# SCH_BO.net
KiCad netlist of a schematic drawn in Altium Designer
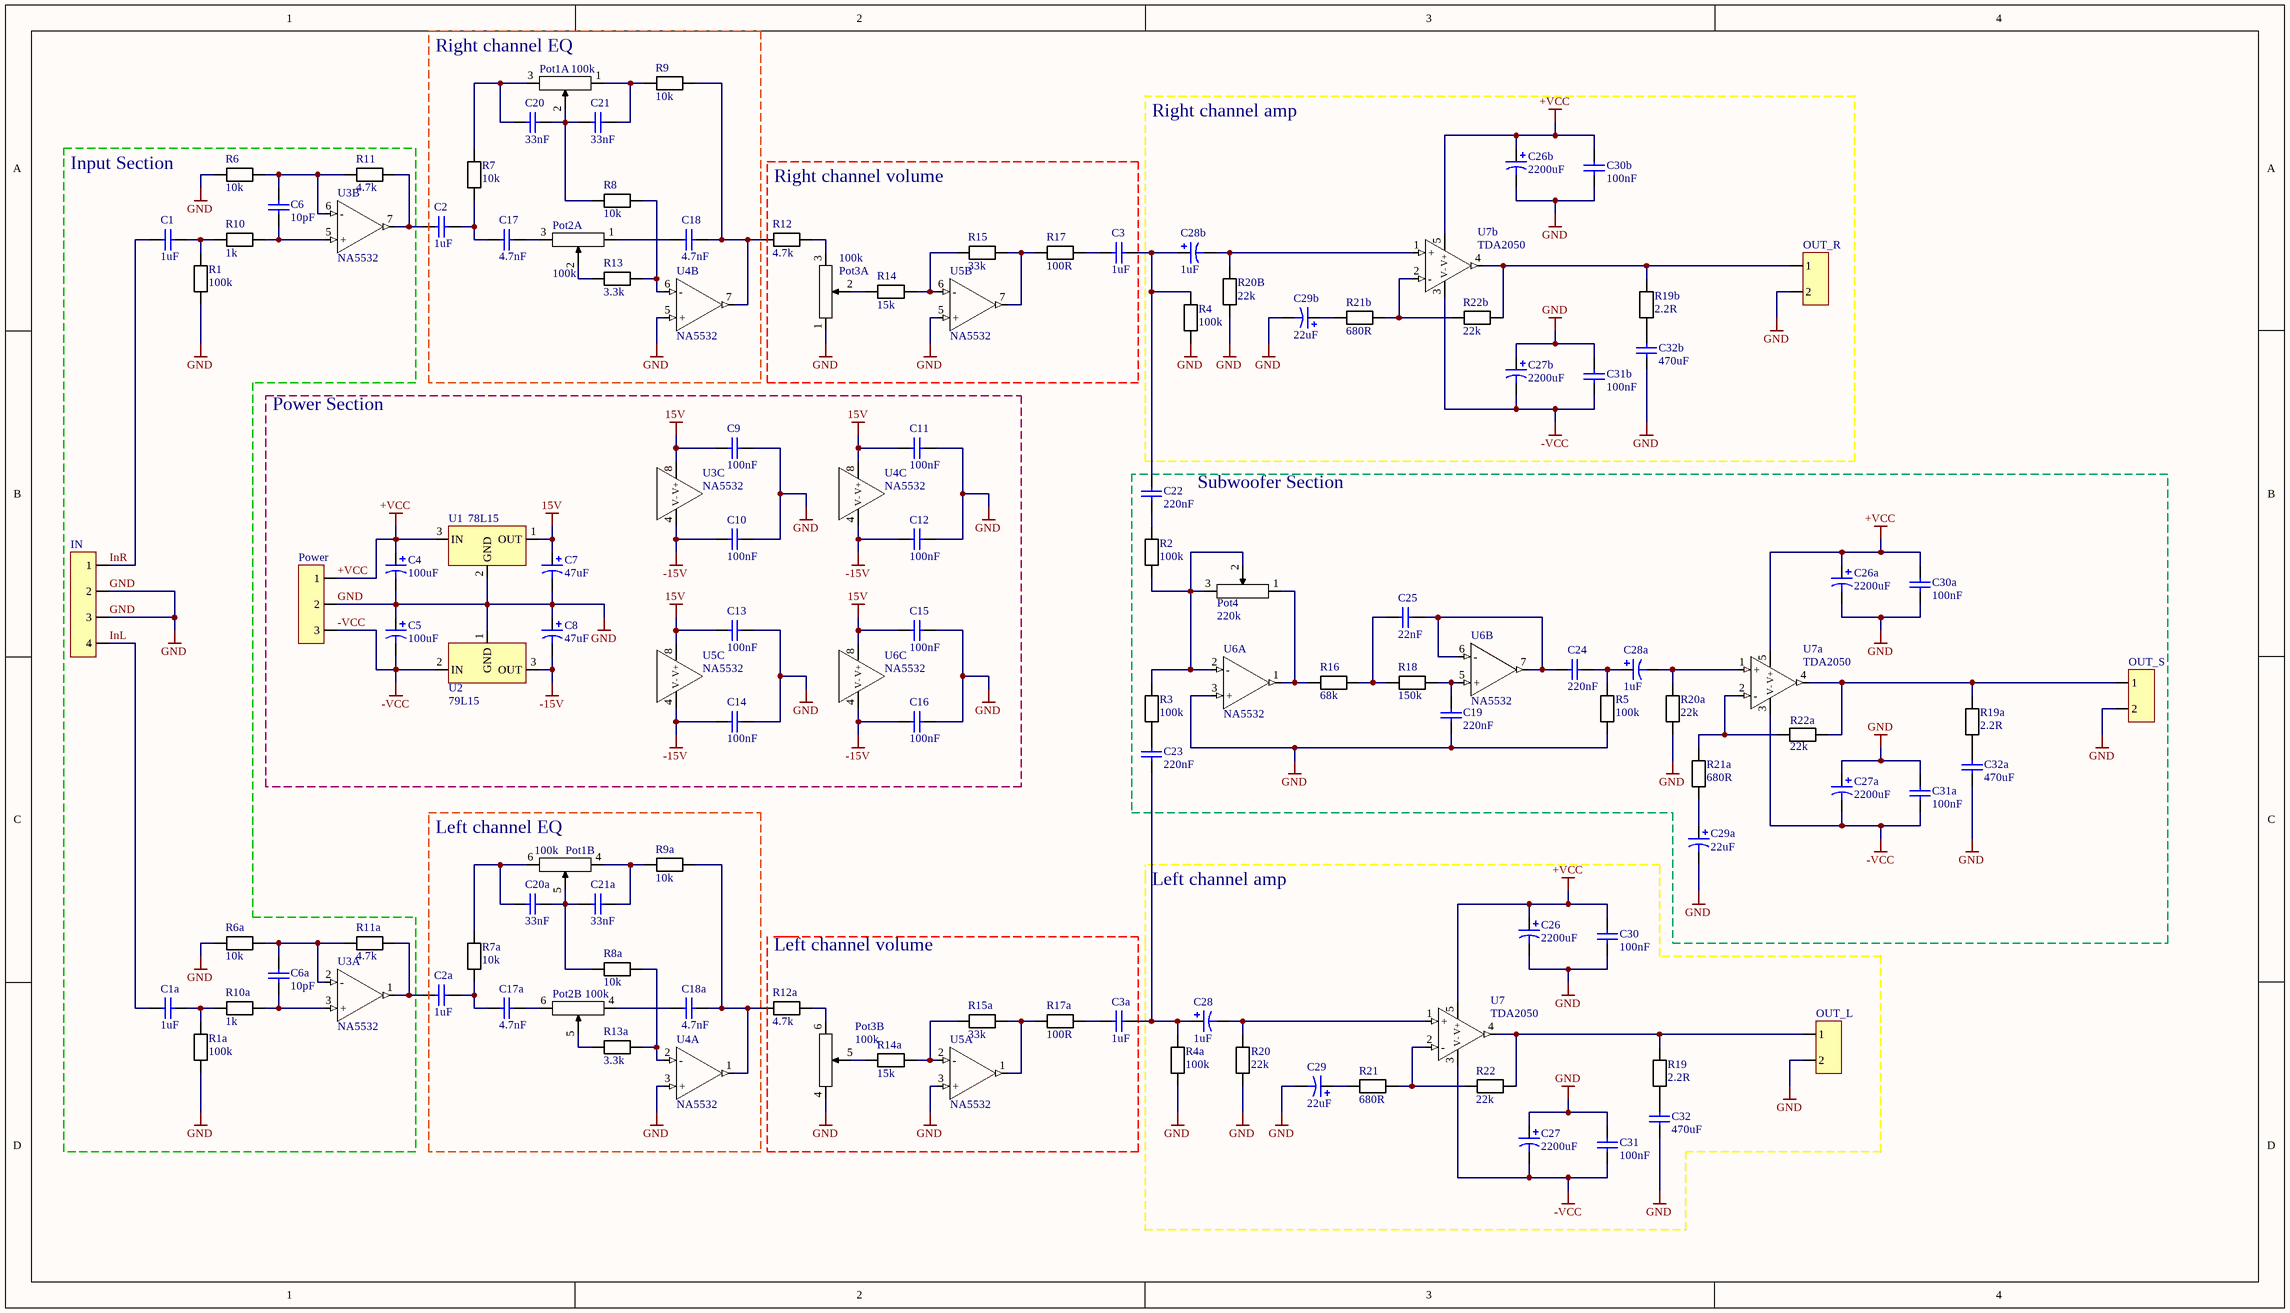
[diagram p0: SCH_BO.SchDoc]

(export (version "E")
  (design (tool "Eeschema 10.0.6"))
  (components
    (comp (ref "C1")
      (value "1uF")
      (footprint "CAP SMD 3.2x1.6x1.6")
      (fields (field (name "Comment") "Capacitor"))
      (libsource (lib "PADS_1") (part "Capacitor"))
    )
    (comp (ref "C1a")
      (value "1uF")
      (footprint "CAP SMD 3.2x1.6x1.6")
      (fields (field (name "Comment") "Capacitor"))
      (libsource (lib "PADS_1") (part "Capacitor"))
    )
    (comp (ref "C2")
      (value "1uF")
      (footprint "CAP SMD 3.2x1.6x1.6")
      (fields (field (name "Comment") "Capacitor"))
      (libsource (lib "PADS_1") (part "Capacitor"))
    )
    (comp (ref "C2a")
      (value "1uF")
      (footprint "CAP SMD 3.2x1.6x1.6")
      (fields (field (name "Comment") "Capacitor"))
      (libsource (lib "PADS_1") (part "Capacitor"))
    )
    (comp (ref "C3")
      (value "1uF")
      (footprint "CAP SMD 3.2x1.6x1.6")
      (fields (field (name "Comment") "Capacitor"))
      (libsource (lib "PADS_1") (part "Capacitor"))
    )
    (comp (ref "C3a")
      (value "1uF")
      (footprint "CAP SMD 3.2x1.6x1.6")
      (fields (field (name "Comment") "Capacitor"))
      (libsource (lib "PADS_1") (part "Capacitor"))
    )
    (comp (ref "C4")
      (value "100uF")
      (footprint "CAP_POL_SMD_8.5x8.5x10.7")
      (fields (field (name "Comment") "Capacitor_Pol"))
      (libsource (lib "PADS_1") (part "Capacitor_Pol"))
    )
    (comp (ref "C5")
      (value "100uF")
      (footprint "CAP_POL_SMD_8.5x8.5x10.7")
      (fields (field (name "Comment") "Capacitor_Pol"))
      (libsource (lib "PADS_1") (part "Capacitor_Pol"))
    )
    (comp (ref "C6")
      (value "10pF")
      (footprint "CAP SMD 2x1.25x1.25")
      (fields (field (name "Comment") "Capacitor"))
      (libsource (lib "PADS_1_1") (part "Capacitor"))
    )
    (comp (ref "C6a")
      (value "10pF")
      (footprint "CAP SMD 2x1.25x1.25")
      (fields (field (name "Comment") "Capacitor"))
      (libsource (lib "PADS_1_1") (part "Capacitor"))
    )
    (comp (ref "C7")
      (value "47uF")
      (footprint "CAP_POL_SMD_6.8x6.8x8")
      (fields (field (name "Comment") "Capacitor_Pol"))
      (libsource (lib "PADS_1") (part "Capacitor_Pol"))
    )
    (comp (ref "C8")
      (value "47uF")
      (footprint "CAP_POL_SMD_6.8x6.8x8")
      (fields (field (name "Comment") "Capacitor_Pol"))
      (libsource (lib "PADS_1") (part "Capacitor_Pol"))
    )
    (comp (ref "C9")
      (value "100nF")
      (footprint "CAP SMD 2x1.25x1.25")
      (fields (field (name "Comment") "Capacitor"))
      (libsource (lib "PADS_1") (part "Capacitor"))
    )
    (comp (ref "C10")
      (value "100nF")
      (footprint "CAP SMD 2x1.25x1.25")
      (fields (field (name "Comment") "Capacitor"))
      (libsource (lib "PADS_1") (part "Capacitor"))
    )
    (comp (ref "C11")
      (value "100nF")
      (footprint "CAP SMD 2x1.25x1.25")
      (fields (field (name "Comment") "Capacitor"))
      (libsource (lib "PADS_1") (part "Capacitor"))
    )
    (comp (ref "C12")
      (value "100nF")
      (footprint "CAP SMD 2x1.25x1.25")
      (fields (field (name "Comment") "Capacitor"))
      (libsource (lib "PADS_1") (part "Capacitor"))
    )
    (comp (ref "C13")
      (value "100nF")
      (footprint "CAP SMD 2x1.25x1.25")
      (fields (field (name "Comment") "Capacitor"))
      (libsource (lib "PADS_1") (part "Capacitor"))
    )
    (comp (ref "C14")
      (value "100nF")
      (footprint "CAP SMD 2x1.25x1.25")
      (fields (field (name "Comment") "Capacitor"))
      (libsource (lib "PADS_1") (part "Capacitor"))
    )
    (comp (ref "C15")
      (value "100nF")
      (footprint "CAP SMD 2x1.25x1.25")
      (fields (field (name "Comment") "Capacitor"))
      (libsource (lib "PADS_1") (part "Capacitor"))
    )
    (comp (ref "C16")
      (value "100nF")
      (footprint "CAP SMD 2x1.25x1.25")
      (fields (field (name "Comment") "Capacitor"))
      (libsource (lib "PADS_1") (part "Capacitor"))
    )
    (comp (ref "C17")
      (value "4.7nF")
      (footprint "CAP SMD 2x1.25x1.25")
      (fields (field (name "Comment") "Capacitor"))
      (libsource (lib "PADS_1") (part "Capacitor"))
    )
    (comp (ref "C17a")
      (value "4.7nF")
      (footprint "CAP SMD 2x1.25x1.25")
      (fields (field (name "Comment") "Capacitor"))
      (libsource (lib "PADS_1") (part "Capacitor"))
    )
    (comp (ref "C18")
      (value "4.7nF")
      (footprint "CAP SMD 2x1.25x1.25")
      (fields (field (name "Comment") "Capacitor"))
      (libsource (lib "PADS_1") (part "Capacitor"))
    )
    (comp (ref "C18a")
      (value "4.7nF")
      (footprint "CAP SMD 2x1.25x1.25")
      (fields (field (name "Comment") "Capacitor"))
      (libsource (lib "PADS_1") (part "Capacitor"))
    )
    (comp (ref "C19")
      (value "220nF")
      (footprint "CAP SMD 2x1.25x1.25")
      (fields (field (name "Comment") "Capacitor"))
      (libsource (lib "PADS_1_1") (part "Capacitor"))
    )
    (comp (ref "C20")
      (value "33nF")
      (footprint "CAP SMD 2x1.25x1.25")
      (fields (field (name "Comment") "Capacitor"))
      (libsource (lib "PADS_1_1") (part "Capacitor"))
    )
    (comp (ref "C20a")
      (value "33nF")
      (footprint "CAP SMD 2x1.25x1.25")
      (fields (field (name "Comment") "Capacitor"))
      (libsource (lib "PADS_1_1") (part "Capacitor"))
    )
    (comp (ref "C21")
      (value "33nF")
      (footprint "CAP SMD 2x1.25x1.25")
      (fields (field (name "Comment") "Capacitor"))
      (libsource (lib "PADS_1_1") (part "Capacitor"))
    )
    (comp (ref "C21a")
      (value "33nF")
      (footprint "CAP SMD 2x1.25x1.25")
      (fields (field (name "Comment") "Capacitor"))
      (libsource (lib "PADS_1_1") (part "Capacitor"))
    )
    (comp (ref "C22")
      (value "220nF")
      (footprint "CAP SMD 2x1.25x1.25")
      (fields (field (name "Comment") "Capacitor"))
      (libsource (lib "PADS_1_1") (part "Capacitor"))
    )
    (comp (ref "C23")
      (value "220nF")
      (footprint "CAP SMD 2x1.25x1.25")
      (fields (field (name "Comment") "Capacitor"))
      (libsource (lib "PADS_1_1") (part "Capacitor"))
    )
    (comp (ref "C24")
      (value "220nF")
      (footprint "CAP SMD 2x1.25x1.25")
      (fields (field (name "Comment") "Capacitor"))
      (libsource (lib "PADS_1_1") (part "Capacitor"))
    )
    (comp (ref "C25")
      (value "22nF")
      (footprint "CAP SMD 2x1.25x1.25")
      (fields (field (name "Comment") "Capacitor"))
      (libsource (lib "PADS_1_1") (part "Capacitor"))
    )
    (comp (ref "C26")
      (value "2200uF")
      (footprint "Panasonic_K16_BO")
      (fields (field (name "Comment") "Capacitor_Pol"))
      (libsource (lib "PADS_1") (part "Capacitor_Pol"))
    )
    (comp (ref "C26a")
      (value "2200uF")
      (footprint "Panasonic_K16_BO")
      (fields (field (name "Comment") "Capacitor_Pol"))
      (libsource (lib "PADS_1") (part "Capacitor_Pol"))
    )
    (comp (ref "C26b")
      (value "2200uF")
      (footprint "Panasonic_K16_BO")
      (fields (field (name "Comment") "Capacitor_Pol"))
      (libsource (lib "PADS_1") (part "Capacitor_Pol"))
    )
    (comp (ref "C27")
      (value "2200uF")
      (footprint "Panasonic_K16_BO")
      (fields (field (name "Comment") "Capacitor_Pol"))
      (libsource (lib "PADS_1") (part "Capacitor_Pol"))
    )
    (comp (ref "C27a")
      (value "2200uF")
      (footprint "Panasonic_K16_BO")
      (fields (field (name "Comment") "Capacitor_Pol"))
      (libsource (lib "PADS_1") (part "Capacitor_Pol"))
    )
    (comp (ref "C27b")
      (value "2200uF")
      (footprint "Panasonic_K16_BO")
      (fields (field (name "Comment") "Capacitor_Pol"))
      (libsource (lib "PADS_1") (part "Capacitor_Pol"))
    )
    (comp (ref "C28")
      (value "1uF")
      (footprint "CAP_POL_SMD_4.5x4.5x6")
      (fields (field (name "Comment") "Capacitor_Pol"))
      (libsource (lib "PADS_1") (part "Capacitor_Pol"))
    )
    (comp (ref "C28a")
      (value "1uF")
      (footprint "CAP_POL_SMD_4.5x4.5x6")
      (fields (field (name "Comment") "Capacitor_Pol"))
      (libsource (lib "PADS_1") (part "Capacitor_Pol"))
    )
    (comp (ref "C28b")
      (value "1uF")
      (footprint "CAP_POL_SMD_4.5x4.5x6")
      (fields (field (name "Comment") "Capacitor_Pol"))
      (libsource (lib "PADS_1") (part "Capacitor_Pol"))
    )
    (comp (ref "C29")
      (value "22uF")
      (footprint "CAP_POL_SMD_6.8x6.8x6")
      (fields (field (name "Comment") "Capacitor_Pol"))
      (libsource (lib "PADS_1") (part "Capacitor_Pol"))
    )
    (comp (ref "C29a")
      (value "22uF")
      (footprint "CAP_POL_SMD_6.8x6.8x6")
      (fields (field (name "Comment") "Capacitor_Pol"))
      (libsource (lib "PADS_1") (part "Capacitor_Pol"))
    )
    (comp (ref "C29b")
      (value "22uF")
      (footprint "CAP_POL_SMD_6.8x6.8x6")
      (fields (field (name "Comment") "Capacitor_Pol"))
      (libsource (lib "PADS_1") (part "Capacitor_Pol"))
    )
    (comp (ref "C30")
      (value "100nF")
      (footprint "CAP SMD 2x1.25x1.25")
      (fields (field (name "Comment") "Capacitor"))
      (libsource (lib "PADS_1") (part "Capacitor"))
    )
    (comp (ref "C30a")
      (value "100nF")
      (footprint "CAP SMD 2x1.25x1.25")
      (fields (field (name "Comment") "Capacitor"))
      (libsource (lib "PADS_1") (part "Capacitor"))
    )
    (comp (ref "C30b")
      (value "100nF")
      (footprint "CAP SMD 2x1.25x1.25")
      (fields (field (name "Comment") "Capacitor"))
      (libsource (lib "PADS_1") (part "Capacitor"))
    )
    (comp (ref "C31")
      (value "100nF")
      (footprint "CAP SMD 2x1.25x1.25")
      (fields (field (name "Comment") "Capacitor"))
      (libsource (lib "PADS_1") (part "Capacitor"))
    )
    (comp (ref "C31a")
      (value "100nF")
      (footprint "CAP SMD 2x1.25x1.25")
      (fields (field (name "Comment") "Capacitor"))
      (libsource (lib "PADS_1") (part "Capacitor"))
    )
    (comp (ref "C31b")
      (value "100nF")
      (footprint "CAP SMD 2x1.25x1.25")
      (fields (field (name "Comment") "Capacitor"))
      (libsource (lib "PADS_1") (part "Capacitor"))
    )
    (comp (ref "C32")
      (value "470uF")
      (footprint "CAP SMD 2x1.25x1.25")
      (fields (field (name "Comment") "Capacitor"))
      (libsource (lib "PADS_1") (part "Capacitor"))
    )
    (comp (ref "C32a")
      (value "470uF")
      (footprint "CAP SMD 2x1.25x1.25")
      (fields (field (name "Comment") "Capacitor"))
      (libsource (lib "PADS_1") (part "Capacitor"))
    )
    (comp (ref "C32b")
      (value "470uF")
      (footprint "CAP SMD 2x1.25x1.25")
      (fields (field (name "Comment") "Capacitor"))
      (libsource (lib "PADS_1") (part "Capacitor"))
    )
    (comp (ref "IN")
      (value "~")
      (footprint "quad solder pad")
      (libsource (lib "PADS_1") (part "Quad solder pad"))
    )
    (comp (ref "OUT_L")
      (value "?")
      (footprint "double solder pad")
      (libsource (lib "PADS_1") (part "Double solder pad"))
    )
    (comp (ref "OUT_R")
      (value "?")
      (footprint "double solder pad")
      (libsource (lib "PADS_1") (part "Double solder pad"))
    )
    (comp (ref "OUT_S")
      (value "?")
      (footprint "double solder pad")
      (libsource (lib "PADS_1") (part "Double solder pad"))
    )
    (comp (ref "Pot1")
      (value "?")
      (footprint "PDB182-K_BO")
      (fields (field (name "ALTIUM_UNNAMED_1") "100k"))
      (libsource (lib "PADS_1_1") (part "BOURNS_PDB182-K"))
    )
    (comp (ref "Pot2")
      (value "?")
      (footprint "PDB182-K_BO")
      (fields (field (name "ALTIUM_UNNAMED_1") "100k"))
      (libsource (lib "PADS_1_1") (part "BOURNS_PDB182-K"))
    )
    (comp (ref "Pot3")
      (value "?")
      (footprint "PDB182-K_BO")
      (fields (field (name "ALTIUM_UNNAMED_1") "100k"))
      (libsource (lib "") (part "BOURNS_PDB182-K_1"))
    )
    (comp (ref "Pot4")
      (value "~")
      (footprint "PDB181-K_BO")
      (fields (field (name "ALTIUM_UNNAMED_1") "220k"))
      (libsource (lib "PADS_1_1") (part "BOURNS_PDB181-K"))
    )
    (comp (ref "Power")
      (value "?")
      (footprint "tripple solder pad")
      (libsource (lib "PADS_1_1") (part "Tripple solder pad"))
    )
    (comp (ref "R1")
      (value "100k")
      (footprint "RES_SMD_3.1x1.6x0.6")
      (description "Resistor")
      (fields (field (name "PUBLISHER") "Altium Limited"))
      (libsource (lib "PADS_1") (part "Resistor"))
    )
    (comp (ref "R1a")
      (value "100k")
      (footprint "RES_SMD_3.1x1.6x0.6")
      (description "Resistor")
      (fields (field (name "PUBLISHER") "Altium Limited"))
      (libsource (lib "PADS_1") (part "Resistor"))
    )
    (comp (ref "R2")
      (value "100k")
      (footprint "RES_SMD_3.1x1.6x0.6")
      (description "Resistor")
      (fields (field (name "PUBLISHER") "Altium Limited"))
      (libsource (lib "PADS_1") (part "Resistor"))
    )
    (comp (ref "R3")
      (value "100k")
      (footprint "RES_SMD_3.1x1.6x0.6")
      (description "Resistor")
      (fields (field (name "PUBLISHER") "Altium Limited"))
      (libsource (lib "PADS_1") (part "Resistor"))
    )
    (comp (ref "R4")
      (value "100k")
      (footprint "RES_SMD_3.1x1.6x0.6")
      (description "Resistor")
      (fields (field (name "PUBLISHER") "Altium Limited"))
      (libsource (lib "PADS_1") (part "Resistor"))
    )
    (comp (ref "R4a")
      (value "100k")
      (footprint "RES_SMD_3.1x1.6x0.6")
      (description "Resistor")
      (fields (field (name "PUBLISHER") "Altium Limited"))
      (libsource (lib "PADS_1") (part "Resistor"))
    )
    (comp (ref "R5")
      (value "100k")
      (footprint "RES_SMD_3.1x1.6x0.6")
      (description "Resistor")
      (fields (field (name "PUBLISHER") "Altium Limited"))
      (libsource (lib "PADS_1") (part "Resistor"))
    )
    (comp (ref "R6")
      (value "10k")
      (footprint "RES_SMD_3.1x1.6x0.6")
      (description "Resistor")
      (fields (field (name "PUBLISHER") "Altium Limited"))
      (libsource (lib "PADS_1") (part "Resistor"))
    )
    (comp (ref "R6a")
      (value "10k")
      (footprint "RES_SMD_3.1x1.6x0.6")
      (description "Resistor")
      (fields (field (name "PUBLISHER") "Altium Limited"))
      (libsource (lib "PADS_1") (part "Resistor"))
    )
    (comp (ref "R7")
      (value "10k")
      (footprint "RES_SMD_3.1x1.6x0.6")
      (description "Resistor")
      (fields (field (name "PUBLISHER") "Altium Limited"))
      (libsource (lib "PADS_1") (part "Resistor"))
    )
    (comp (ref "R7a")
      (value "10k")
      (footprint "RES_SMD_3.1x1.6x0.6")
      (description "Resistor")
      (fields (field (name "PUBLISHER") "Altium Limited"))
      (libsource (lib "PADS_1") (part "Resistor"))
    )
    (comp (ref "R8")
      (value "10k")
      (footprint "RES_SMD_3.1x1.6x0.6")
      (description "Resistor")
      (fields (field (name "PUBLISHER") "Altium Limited"))
      (libsource (lib "PADS_1") (part "Resistor"))
    )
    (comp (ref "R8a")
      (value "10k")
      (footprint "RES_SMD_3.1x1.6x0.6")
      (description "Resistor")
      (fields (field (name "PUBLISHER") "Altium Limited"))
      (libsource (lib "PADS_1") (part "Resistor"))
    )
    (comp (ref "R9")
      (value "10k")
      (footprint "RES_SMD_3.1x1.6x0.6")
      (description "Resistor")
      (fields (field (name "PUBLISHER") "Altium Limited"))
      (libsource (lib "PADS_1") (part "Resistor"))
    )
    (comp (ref "R9a")
      (value "10k")
      (footprint "RES_SMD_3.1x1.6x0.6")
      (description "Resistor")
      (fields (field (name "PUBLISHER") "Altium Limited"))
      (libsource (lib "PADS_1") (part "Resistor"))
    )
    (comp (ref "R10")
      (value "1k")
      (footprint "RES_SMD_3.1x1.6x0.6")
      (description "Resistor")
      (fields (field (name "PUBLISHER") "Altium Limited"))
      (libsource (lib "PADS_1") (part "Resistor"))
    )
    (comp (ref "R10a")
      (value "1k")
      (footprint "RES_SMD_3.1x1.6x0.6")
      (description "Resistor")
      (fields (field (name "PUBLISHER") "Altium Limited"))
      (libsource (lib "PADS_1") (part "Resistor"))
    )
    (comp (ref "R11")
      (value "4.7k")
      (footprint "RES_SMD_3.1x1.6x0.6")
      (description "Resistor")
      (fields (field (name "PUBLISHER") "Altium Limited"))
      (libsource (lib "PADS_1") (part "Resistor"))
    )
    (comp (ref "R11a")
      (value "4.7k")
      (footprint "RES_SMD_3.1x1.6x0.6")
      (description "Resistor")
      (fields (field (name "PUBLISHER") "Altium Limited"))
      (libsource (lib "PADS_1") (part "Resistor"))
    )
    (comp (ref "R12")
      (value "4.7k")
      (footprint "RES_SMD_3.1x1.6x0.6")
      (description "Resistor")
      (fields (field (name "PUBLISHER") "Altium Limited"))
      (libsource (lib "PADS_1") (part "Resistor"))
    )
    (comp (ref "R12a")
      (value "4.7k")
      (footprint "RES_SMD_3.1x1.6x0.6")
      (description "Resistor")
      (fields (field (name "PUBLISHER") "Altium Limited"))
      (libsource (lib "PADS_1") (part "Resistor"))
    )
    (comp (ref "R13")
      (value "3.3k")
      (footprint "RES_SMD_3.1x1.6x0.6")
      (description "Resistor")
      (fields (field (name "PUBLISHER") "Altium Limited"))
      (libsource (lib "PADS_1") (part "Resistor"))
    )
    (comp (ref "R13a")
      (value "3.3k")
      (footprint "RES_SMD_3.1x1.6x0.6")
      (description "Resistor")
      (fields (field (name "PUBLISHER") "Altium Limited"))
      (libsource (lib "PADS_1") (part "Resistor"))
    )
    (comp (ref "R14")
      (value "15k")
      (footprint "RES_SMD_3.1x1.6x0.6")
      (description "Resistor")
      (fields (field (name "PUBLISHER") "Altium Limited"))
      (libsource (lib "PADS_1") (part "Resistor"))
    )
    (comp (ref "R14a")
      (value "15k")
      (footprint "RES_SMD_3.1x1.6x0.6")
      (description "Resistor")
      (fields (field (name "PUBLISHER") "Altium Limited"))
      (libsource (lib "PADS_1") (part "Resistor"))
    )
    (comp (ref "R15")
      (value "33k")
      (footprint "RES_SMD_3.1x1.6x0.6")
      (description "Resistor")
      (fields (field (name "PUBLISHER") "Altium Limited"))
      (libsource (lib "PADS_1") (part "Resistor"))
    )
    (comp (ref "R15a")
      (value "33k")
      (footprint "RES_SMD_3.1x1.6x0.6")
      (description "Resistor")
      (fields (field (name "PUBLISHER") "Altium Limited"))
      (libsource (lib "PADS_1") (part "Resistor"))
    )
    (comp (ref "R16")
      (value "68k")
      (footprint "RES_SMD_3.1x1.6x0.6")
      (description "Resistor")
      (fields (field (name "PUBLISHER") "Altium Limited"))
      (libsource (lib "PADS_1") (part "Resistor"))
    )
    (comp (ref "R17")
      (value "100R")
      (footprint "RES_SMD_3.1x1.6x0.6")
      (description "Resistor")
      (fields (field (name "PUBLISHER") "Altium Limited"))
      (libsource (lib "PADS_1") (part "Resistor"))
    )
    (comp (ref "R17a")
      (value "100R")
      (footprint "RES_SMD_3.1x1.6x0.6")
      (description "Resistor")
      (fields (field (name "PUBLISHER") "Altium Limited"))
      (libsource (lib "PADS_1") (part "Resistor"))
    )
    (comp (ref "R18")
      (value "150k")
      (footprint "RES_SMD_3.1x1.6x0.6")
      (description "Resistor")
      (fields (field (name "PUBLISHER") "Altium Limited"))
      (libsource (lib "PADS_1") (part "Resistor"))
    )
    (comp (ref "R19")
      (value "2.2R")
      (footprint "RES_SMD_3.1x1.6x0.6")
      (description "Resistor")
      (fields (field (name "PUBLISHER") "Altium Limited"))
      (libsource (lib "PADS_1") (part "Resistor"))
    )
    (comp (ref "R19a")
      (value "2.2R")
      (footprint "RES_SMD_3.1x1.6x0.6")
      (description "Resistor")
      (fields (field (name "PUBLISHER") "Altium Limited"))
      (libsource (lib "PADS_1") (part "Resistor"))
    )
    (comp (ref "R19b")
      (value "2.2R")
      (footprint "RES_SMD_3.1x1.6x0.6")
      (description "Resistor")
      (fields (field (name "PUBLISHER") "Altium Limited"))
      (libsource (lib "PADS_1") (part "Resistor"))
    )
    (comp (ref "R20")
      (value "22k")
      (footprint "RES_SMD_3.1x1.6x0.6")
      (description "Resistor")
      (fields (field (name "PUBLISHER") "Altium Limited"))
      (libsource (lib "PADS_1") (part "Resistor"))
    )
    (comp (ref "R20a")
      (value "22k")
      (footprint "RES_SMD_3.1x1.6x0.6")
      (description "Resistor")
      (fields (field (name "PUBLISHER") "Altium Limited"))
      (libsource (lib "PADS_1") (part "Resistor"))
    )
    (comp (ref "R20B")
      (value "22k")
      (footprint "RES_SMD_3.1x1.6x0.6")
      (description "Resistor")
      (fields (field (name "PUBLISHER") "Altium Limited"))
      (libsource (lib "PADS_1") (part "Resistor"))
    )
    (comp (ref "R21")
      (value "680R")
      (footprint "RES_SMD_3.1x1.6x0.6")
      (description "Resistor")
      (fields (field (name "PUBLISHER") "Altium Limited"))
      (libsource (lib "PADS_1") (part "Resistor"))
    )
    (comp (ref "R21a")
      (value "680R")
      (footprint "RES_SMD_3.1x1.6x0.6")
      (description "Resistor")
      (fields (field (name "PUBLISHER") "Altium Limited"))
      (libsource (lib "PADS_1") (part "Resistor"))
    )
    (comp (ref "R21b")
      (value "680R")
      (footprint "RES_SMD_3.1x1.6x0.6")
      (description "Resistor")
      (fields (field (name "PUBLISHER") "Altium Limited"))
      (libsource (lib "PADS_1") (part "Resistor"))
    )
    (comp (ref "R22")
      (value "22k")
      (footprint "RES_SMD_3.1x1.6x0.6")
      (description "Resistor")
      (fields (field (name "PUBLISHER") "Altium Limited"))
      (libsource (lib "PADS_1") (part "Resistor"))
    )
    (comp (ref "R22a")
      (value "22k")
      (footprint "RES_SMD_3.1x1.6x0.6")
      (description "Resistor")
      (fields (field (name "PUBLISHER") "Altium Limited"))
      (libsource (lib "PADS_1") (part "Resistor"))
    )
    (comp (ref "R22b")
      (value "22k")
      (footprint "RES_SMD_3.1x1.6x0.6")
      (description "Resistor")
      (fields (field (name "PUBLISHER") "Altium Limited"))
      (libsource (lib "PADS_1") (part "Resistor"))
    )
    (comp (ref "U1") (value "78L15") (footprint "SOT89") (libsource (lib "PADS_1_1") (part "78L15")))
    (comp (ref "U2") (value "79L15") (footprint "SOT89") (libsource (lib "PADS_1_1") (part "79L15")))
    (comp (ref "U3") (value "NA5532") (footprint "SOT96-1") (libsource (lib "PADS_1_1") (part "NA5532")))
    (comp (ref "U4") (value "NA5532") (footprint "SOT96-1") (libsource (lib "PADS_1_1") (part "NA5532")))
    (comp (ref "U5") (value "NA5532") (footprint "SOT96-1") (libsource (lib "PADS_1_1") (part "NA5532")))
    (comp (ref "U6") (value "NA5532") (footprint "SOT96-1") (libsource (lib "PADS_1_1") (part "NA5532")))
    (comp (ref "U7") (value "TDA2050") (footprint "TO-22B_BO") (libsource (lib "PADS_1") (part "TDA2050")))
    (comp (ref "U7a") (value "TDA2050") (footprint "TO-22B_BO") (libsource (lib "PADS_1") (part "TDA2050")))
    (comp (ref "U7b") (value "TDA2050") (footprint "TO-22B_BO") (libsource (lib "PADS_1") (part "TDA2050")))
  )
  (nets
    (net (code "1") (name "+VCC") (class "Default")
      (node (ref "C26") (pin "1") (pinfunction "1_1") (pintype "passive"))
      (node (ref "C26a") (pin "1") (pinfunction "1_1") (pintype "passive"))
      (node (ref "C26b") (pin "1") (pinfunction "1_1") (pintype "passive"))
      (node (ref "C30") (pin "1") (pinfunction "1_1") (pintype "passive"))
      (node (ref "C30a") (pin "1") (pinfunction "1_1") (pintype "passive"))
      (node (ref "C30b") (pin "1") (pinfunction "1_1") (pintype "passive"))
      (node (ref "C4") (pin "1") (pinfunction "1_1") (pintype "passive"))
      (node (ref "Power") (pin "1") (pinfunction "1_1") (pintype "passive"))
      (node (ref "U1") (pin "3") (pinfunction "IN_3") (pintype "passive"))
      (node (ref "U7") (pin "5") (pinfunction "V+_5") (pintype "power_in"))
      (node (ref "U7a") (pin "5") (pinfunction "V+_5") (pintype "power_in"))
      (node (ref "U7b") (pin "5") (pinfunction "V+_5") (pintype "power_in"))
    )
    (net (code "2") (name "-15V") (class "Default")
      (node (ref "C10") (pin "1") (pinfunction "1_1") (pintype "passive"))
      (node (ref "C12") (pin "1") (pinfunction "1_1") (pintype "passive"))
      (node (ref "C14") (pin "1") (pinfunction "1_1") (pintype "passive"))
      (node (ref "C16") (pin "1") (pinfunction "1_1") (pintype "passive"))
      (node (ref "C8") (pin "2") (pinfunction "2_2") (pintype "passive"))
      (node (ref "U2") (pin "3") (pinfunction "OUT_3") (pintype "passive"))
      (node (ref "U3") (pin "4") (pinfunction "V-_4") (pintype "power_in"))
      (node (ref "U4") (pin "4") (pinfunction "V-_4") (pintype "power_in"))
      (node (ref "U5") (pin "4") (pinfunction "V-_4") (pintype "power_in"))
      (node (ref "U6") (pin "4") (pinfunction "V-_4") (pintype "power_in"))
    )
    (net (code "3") (name "-VCC") (class "Default")
      (node (ref "C27") (pin "2") (pinfunction "2_2") (pintype "passive"))
      (node (ref "C27a") (pin "2") (pinfunction "2_2") (pintype "passive"))
      (node (ref "C27b") (pin "2") (pinfunction "2_2") (pintype "passive"))
      (node (ref "C31") (pin "1") (pinfunction "1_1") (pintype "passive"))
      (node (ref "C31a") (pin "1") (pinfunction "1_1") (pintype "passive"))
      (node (ref "C31b") (pin "1") (pinfunction "1_1") (pintype "passive"))
      (node (ref "C5") (pin "2") (pinfunction "2_2") (pintype "passive"))
      (node (ref "Power") (pin "3") (pinfunction "3_3") (pintype "passive"))
      (node (ref "U2") (pin "2") (pinfunction "IN_2") (pintype "passive"))
      (node (ref "U7") (pin "3") (pinfunction "V-_3") (pintype "power_in"))
      (node (ref "U7a") (pin "3") (pinfunction "V-_3") (pintype "power_in"))
      (node (ref "U7b") (pin "3") (pinfunction "V-_3") (pintype "power_in"))
    )
    (net (code "4") (name "/InL") (class "Default")
      (node (ref "C1a") (pin "1") (pinfunction "1_1") (pintype "passive"))
      (node (ref "IN") (pin "4") (pinfunction "4_4") (pintype "passive"))
    )
    (net (code "5") (name "/InR") (class "Default")
      (node (ref "C1") (pin "1") (pinfunction "1_1") (pintype "passive"))
      (node (ref "IN") (pin "1") (pinfunction "1_1") (pintype "passive"))
    )
    (net (code "6") (name "15V") (class "Default")
      (node (ref "C11") (pin "1") (pinfunction "1_1") (pintype "passive"))
      (node (ref "C13") (pin "1") (pinfunction "1_1") (pintype "passive"))
      (node (ref "C15") (pin "1") (pinfunction "1_1") (pintype "passive"))
      (node (ref "C7") (pin "1") (pinfunction "1_1") (pintype "passive"))
      (node (ref "C9") (pin "1") (pinfunction "1_1") (pintype "passive"))
      (node (ref "U1") (pin "1") (pinfunction "OUT_1") (pintype "passive"))
      (node (ref "U3") (pin "8") (pinfunction "V+_8") (pintype "power_in"))
      (node (ref "U4") (pin "8") (pinfunction "V+_8") (pintype "power_in"))
      (node (ref "U5") (pin "8") (pinfunction "V+_8") (pintype "power_in"))
      (node (ref "U6") (pin "8") (pinfunction "V+_8") (pintype "power_in"))
    )
    (net (code "7") (name "GND") (class "Default")
      (node (ref "C10") (pin "2") (pinfunction "2_2") (pintype "passive"))
      (node (ref "C11") (pin "2") (pinfunction "2_2") (pintype "passive"))
      (node (ref "C12") (pin "2") (pinfunction "2_2") (pintype "passive"))
      (node (ref "C13") (pin "2") (pinfunction "2_2") (pintype "passive"))
      (node (ref "C14") (pin "2") (pinfunction "2_2") (pintype "passive"))
      (node (ref "C15") (pin "2") (pinfunction "2_2") (pintype "passive"))
      (node (ref "C16") (pin "2") (pinfunction "2_2") (pintype "passive"))
      (node (ref "C19") (pin "2") (pinfunction "2_2") (pintype "passive"))
      (node (ref "C26") (pin "2") (pinfunction "2_2") (pintype "passive"))
      (node (ref "C26a") (pin "2") (pinfunction "2_2") (pintype "passive"))
      (node (ref "C26b") (pin "2") (pinfunction "2_2") (pintype "passive"))
      (node (ref "C27") (pin "1") (pinfunction "1_1") (pintype "passive"))
      (node (ref "C27a") (pin "1") (pinfunction "1_1") (pintype "passive"))
      (node (ref "C27b") (pin "1") (pinfunction "1_1") (pintype "passive"))
      (node (ref "C29") (pin "2") (pinfunction "2_2") (pintype "passive"))
      (node (ref "C29a") (pin "2") (pinfunction "2_2") (pintype "passive"))
      (node (ref "C29b") (pin "2") (pinfunction "2_2") (pintype "passive"))
      (node (ref "C30") (pin "2") (pinfunction "2_2") (pintype "passive"))
      (node (ref "C30a") (pin "2") (pinfunction "2_2") (pintype "passive"))
      (node (ref "C30b") (pin "2") (pinfunction "2_2") (pintype "passive"))
      (node (ref "C31") (pin "2") (pinfunction "2_2") (pintype "passive"))
      (node (ref "C31a") (pin "2") (pinfunction "2_2") (pintype "passive"))
      (node (ref "C31b") (pin "2") (pinfunction "2_2") (pintype "passive"))
      (node (ref "C32") (pin "1") (pinfunction "1_1") (pintype "passive"))
      (node (ref "C32a") (pin "1") (pinfunction "1_1") (pintype "passive"))
      (node (ref "C32b") (pin "1") (pinfunction "1_1") (pintype "passive"))
      (node (ref "C4") (pin "2") (pinfunction "2_2") (pintype "passive"))
      (node (ref "C5") (pin "1") (pinfunction "1_1") (pintype "passive"))
      (node (ref "C7") (pin "2") (pinfunction "2_2") (pintype "passive"))
      (node (ref "C8") (pin "1") (pinfunction "1_1") (pintype "passive"))
      (node (ref "C9") (pin "2") (pinfunction "2_2") (pintype "passive"))
      (node (ref "IN") (pin "2") (pinfunction "2_2") (pintype "passive"))
      (node (ref "IN") (pin "3") (pinfunction "3_3") (pintype "passive"))
      (node (ref "OUT_L") (pin "2") (pinfunction "2_2") (pintype "passive"))
      (node (ref "OUT_R") (pin "2") (pinfunction "2_2") (pintype "passive"))
      (node (ref "OUT_S") (pin "2") (pinfunction "2_2") (pintype "passive"))
      (node (ref "Pot3") (pin "1") (pinfunction "1_1") (pintype "passive"))
      (node (ref "Pot3") (pin "4") (pinfunction "4_4") (pintype "passive"))
      (node (ref "Power") (pin "2") (pinfunction "2_2") (pintype "passive"))
      (node (ref "R1") (pin "1") (pinfunction "OUT_1") (pintype "passive"))
      (node (ref "R1a") (pin "1") (pinfunction "OUT_1") (pintype "passive"))
      (node (ref "R20") (pin "2") (pinfunction "OUT_2") (pintype "passive"))
      (node (ref "R20B") (pin "2") (pinfunction "OUT_2") (pintype "passive"))
      (node (ref "R20a") (pin "2") (pinfunction "OUT_2") (pintype "passive"))
      (node (ref "R4") (pin "2") (pinfunction "OUT_2") (pintype "passive"))
      (node (ref "R4a") (pin "2") (pinfunction "OUT_2") (pintype "passive"))
      (node (ref "R5") (pin "2") (pinfunction "OUT_2") (pintype "passive"))
      (node (ref "R6") (pin "2") (pinfunction "OUT_2") (pintype "passive"))
      (node (ref "R6a") (pin "2") (pinfunction "OUT_2") (pintype "passive"))
      (node (ref "U1") (pin "2") (pinfunction "GND_2") (pintype "passive"))
      (node (ref "U2") (pin "1") (pinfunction "GND_1") (pintype "passive"))
      (node (ref "U4") (pin "3") (pinfunction "+_3") (pintype "input"))
      (node (ref "U4") (pin "5") (pinfunction "+_5") (pintype "input"))
      (node (ref "U5") (pin "3") (pinfunction "+_3") (pintype "input"))
      (node (ref "U5") (pin "5") (pinfunction "+_5") (pintype "input"))
      (node (ref "U6") (pin "3") (pinfunction "+_3") (pintype "input"))
    )
    (net (code "8") (name "Net-(C1-Pad2)") (class "Default")
      (node (ref "C1") (pin "2") (pinfunction "2_2") (pintype "passive"))
      (node (ref "R1") (pin "2") (pinfunction "OUT_2") (pintype "passive"))
      (node (ref "R10") (pin "2") (pinfunction "OUT_2") (pintype "passive"))
    )
    (net (code "9") (name "Net-(C1a-Pad2)") (class "Default")
      (node (ref "C1a") (pin "2") (pinfunction "2_2") (pintype "passive"))
      (node (ref "R10a") (pin "2") (pinfunction "OUT_2") (pintype "passive"))
      (node (ref "R1a") (pin "2") (pinfunction "OUT_2") (pintype "passive"))
    )
    (net (code "10") (name "Net-(C2-Pad1)") (class "Default")
      (node (ref "C2") (pin "1") (pinfunction "1_1") (pintype "passive"))
      (node (ref "R11") (pin "1") (pinfunction "OUT_1") (pintype "passive"))
      (node (ref "U3") (pin "7") (pintype "output"))
    )
    (net (code "11") (name "Net-(C2a-Pad1)") (class "Default")
      (node (ref "C2a") (pin "1") (pinfunction "1_1") (pintype "passive"))
      (node (ref "R11a") (pin "1") (pinfunction "OUT_1") (pintype "passive"))
      (node (ref "U3") (pin "1") (pintype "output"))
    )
    (net (code "12") (name "Net-(C3-Pad1)") (class "Default")
      (node (ref "C3") (pin "1") (pinfunction "1_1") (pintype "passive"))
      (node (ref "R17") (pin "1") (pinfunction "OUT_1") (pintype "passive"))
    )
    (net (code "13") (name "Net-(C3a-Pad1)") (class "Default")
      (node (ref "C3a") (pin "1") (pinfunction "1_1") (pintype "passive"))
      (node (ref "R17a") (pin "1") (pinfunction "OUT_1") (pintype "passive"))
    )
    (net (code "14") (name "Net-(C17-Pad1)") (class "Default")
      (node (ref "C17") (pin "1") (pinfunction "1_1") (pintype "passive"))
      (node (ref "C2") (pin "2") (pinfunction "2_2") (pintype "passive"))
      (node (ref "R7") (pin "2") (pinfunction "OUT_2") (pintype "passive"))
    )
    (net (code "15") (name "Net-(C17-Pad2)") (class "Default")
      (node (ref "C17") (pin "2") (pinfunction "2_2") (pintype "passive"))
      (node (ref "Pot2") (pin "3") (pinfunction "3_3") (pintype "passive"))
    )
    (net (code "16") (name "Net-(C17a-Pad1)") (class "Default")
      (node (ref "C17a") (pin "1") (pinfunction "1_1") (pintype "passive"))
      (node (ref "C2a") (pin "2") (pinfunction "2_2") (pintype "passive"))
      (node (ref "R7a") (pin "2") (pinfunction "OUT_2") (pintype "passive"))
    )
    (net (code "17") (name "Net-(C17a-Pad2)") (class "Default")
      (node (ref "C17a") (pin "2") (pinfunction "2_2") (pintype "passive"))
      (node (ref "Pot2") (pin "6") (pinfunction "6_6") (pintype "passive"))
    )
    (net (code "18") (name "Net-(C18-Pad1)") (class "Default")
      (node (ref "C18") (pin "1") (pinfunction "1_1") (pintype "passive"))
      (node (ref "Pot2") (pin "1") (pinfunction "1_1") (pintype "passive"))
    )
    (net (code "19") (name "Net-(C18-Pad2)") (class "Default")
      (node (ref "C18") (pin "2") (pinfunction "2_2") (pintype "passive"))
      (node (ref "R12") (pin "2") (pinfunction "OUT_2") (pintype "passive"))
      (node (ref "R9") (pin "1") (pinfunction "OUT_1") (pintype "passive"))
      (node (ref "U4") (pin "7") (pintype "output"))
    )
    (net (code "20") (name "Net-(C18a-Pad1)") (class "Default")
      (node (ref "C18a") (pin "1") (pinfunction "1_1") (pintype "passive"))
      (node (ref "Pot2") (pin "4") (pinfunction "4_4") (pintype "passive"))
    )
    (net (code "21") (name "Net-(C18a-Pad2)") (class "Default")
      (node (ref "C18a") (pin "2") (pinfunction "2_2") (pintype "passive"))
      (node (ref "R12a") (pin "2") (pinfunction "OUT_2") (pintype "passive"))
      (node (ref "R9a") (pin "1") (pinfunction "OUT_1") (pintype "passive"))
      (node (ref "U4") (pin "1") (pintype "output"))
    )
    (net (code "22") (name "Net-(C20-Pad1)") (class "Default")
      (node (ref "C20") (pin "1") (pinfunction "1_1") (pintype "passive"))
      (node (ref "C21") (pin "2") (pinfunction "2_2") (pintype "passive"))
      (node (ref "Pot1") (pin "2") (pinfunction "2_2") (pintype "passive"))
      (node (ref "R8") (pin "2") (pinfunction "OUT_2") (pintype "passive"))
    )
    (net (code "23") (name "Net-(C20-Pad2)") (class "Default")
      (node (ref "C20") (pin "2") (pinfunction "2_2") (pintype "passive"))
      (node (ref "Pot1") (pin "3") (pinfunction "3_3") (pintype "passive"))
      (node (ref "R7") (pin "1") (pinfunction "OUT_1") (pintype "passive"))
    )
    (net (code "24") (name "Net-(C20a-Pad1)") (class "Default")
      (node (ref "C20a") (pin "1") (pinfunction "1_1") (pintype "passive"))
      (node (ref "C21a") (pin "2") (pinfunction "2_2") (pintype "passive"))
      (node (ref "Pot1") (pin "5") (pinfunction "5_5") (pintype "passive"))
      (node (ref "R8a") (pin "2") (pinfunction "OUT_2") (pintype "passive"))
    )
    (net (code "25") (name "Net-(C20a-Pad2)") (class "Default")
      (node (ref "C20a") (pin "2") (pinfunction "2_2") (pintype "passive"))
      (node (ref "Pot1") (pin "6") (pinfunction "6_6") (pintype "passive"))
      (node (ref "R7a") (pin "1") (pinfunction "OUT_1") (pintype "passive"))
    )
    (net (code "26") (name "Net-(C21-Pad1)") (class "Default")
      (node (ref "C21") (pin "1") (pinfunction "1_1") (pintype "passive"))
      (node (ref "Pot1") (pin "1") (pinfunction "1_1") (pintype "passive"))
      (node (ref "R9") (pin "2") (pinfunction "OUT_2") (pintype "passive"))
    )
    (net (code "27") (name "Net-(C21a-Pad1)") (class "Default")
      (node (ref "C21a") (pin "1") (pinfunction "1_1") (pintype "passive"))
      (node (ref "Pot1") (pin "4") (pinfunction "4_4") (pintype "passive"))
      (node (ref "R9a") (pin "2") (pinfunction "OUT_2") (pintype "passive"))
    )
    (net (code "28") (name "Net-(C22-Pad1)") (class "Default")
      (node (ref "C22") (pin "1") (pinfunction "1_1") (pintype "passive"))
      (node (ref "R2") (pin "1") (pinfunction "OUT_1") (pintype "passive"))
    )
    (net (code "29") (name "Net-(C22-Pad2)") (class "Default")
      (node (ref "C22") (pin "2") (pinfunction "2_2") (pintype "passive"))
      (node (ref "C28b") (pin "1") (pinfunction "1_1") (pintype "passive"))
      (node (ref "C3") (pin "2") (pinfunction "2_2") (pintype "passive"))
      (node (ref "R4") (pin "1") (pinfunction "OUT_1") (pintype "passive"))
    )
    (net (code "30") (name "Net-(C23-Pad1)") (class "Default")
      (node (ref "C23") (pin "1") (pinfunction "1_1") (pintype "passive"))
      (node (ref "C28") (pin "1") (pinfunction "1_1") (pintype "passive"))
      (node (ref "C3a") (pin "2") (pinfunction "2_2") (pintype "passive"))
      (node (ref "R4a") (pin "1") (pinfunction "OUT_1") (pintype "passive"))
    )
    (net (code "31") (name "Net-(C23-Pad2)") (class "Default")
      (node (ref "C23") (pin "2") (pinfunction "2_2") (pintype "passive"))
      (node (ref "R3") (pin "2") (pinfunction "OUT_2") (pintype "passive"))
    )
    (net (code "32") (name "Net-(C24-Pad2)") (class "Default")
      (node (ref "C24") (pin "2") (pinfunction "2_2") (pintype "passive"))
      (node (ref "C28a") (pin "1") (pinfunction "1_1") (pintype "passive"))
      (node (ref "R5") (pin "1") (pinfunction "OUT_1") (pintype "passive"))
    )
    (net (code "33") (name "Net-(C25-Pad1)") (class "Default")
      (node (ref "C25") (pin "1") (pinfunction "1_1") (pintype "passive"))
      (node (ref "R16") (pin "1") (pinfunction "OUT_1") (pintype "passive"))
      (node (ref "R18") (pin "2") (pinfunction "OUT_2") (pintype "passive"))
    )
    (net (code "34") (name "Net-(C29-Pad1)") (class "Default")
      (node (ref "C29") (pin "1") (pinfunction "1_1") (pintype "passive"))
      (node (ref "R21") (pin "2") (pinfunction "OUT_2") (pintype "passive"))
    )
    (net (code "35") (name "Net-(C29a-Pad1)") (class "Default")
      (node (ref "C29a") (pin "1") (pinfunction "1_1") (pintype "passive"))
      (node (ref "R21a") (pin "2") (pinfunction "OUT_2") (pintype "passive"))
    )
    (net (code "36") (name "Net-(C29b-Pad1)") (class "Default")
      (node (ref "C29b") (pin "1") (pinfunction "1_1") (pintype "passive"))
      (node (ref "R21b") (pin "2") (pinfunction "OUT_2") (pintype "passive"))
    )
    (net (code "37") (name "Net-(C32-Pad2)") (class "Default")
      (node (ref "C32") (pin "2") (pinfunction "2_2") (pintype "passive"))
      (node (ref "R19") (pin "1") (pinfunction "OUT_1") (pintype "passive"))
    )
    (net (code "38") (name "Net-(C32a-Pad2)") (class "Default")
      (node (ref "C32a") (pin "2") (pinfunction "2_2") (pintype "passive"))
      (node (ref "R19a") (pin "1") (pinfunction "OUT_1") (pintype "passive"))
    )
    (net (code "39") (name "Net-(C32b-Pad2)") (class "Default")
      (node (ref "C32b") (pin "2") (pinfunction "2_2") (pintype "passive"))
      (node (ref "R19b") (pin "1") (pinfunction "OUT_1") (pintype "passive"))
    )
    (net (code "40") (name "Net-(OUT_L-Pad1)") (class "Default")
      (node (ref "OUT_L") (pin "1") (pinfunction "1_1") (pintype "passive"))
      (node (ref "R19") (pin "2") (pinfunction "OUT_2") (pintype "passive"))
      (node (ref "R22") (pin "1") (pinfunction "OUT_1") (pintype "passive"))
      (node (ref "U7") (pin "4") (pintype "output"))
    )
    (net (code "41") (name "Net-(OUT_R-Pad1)") (class "Default")
      (node (ref "OUT_R") (pin "1") (pinfunction "1_1") (pintype "passive"))
      (node (ref "R19b") (pin "2") (pinfunction "OUT_2") (pintype "passive"))
      (node (ref "R22b") (pin "1") (pinfunction "OUT_1") (pintype "passive"))
      (node (ref "U7b") (pin "4") (pintype "output"))
    )
    (net (code "42") (name "Net-(OUT_S-Pad1)") (class "Default")
      (node (ref "OUT_S") (pin "1") (pinfunction "1_1") (pintype "passive"))
      (node (ref "R19a") (pin "2") (pinfunction "OUT_2") (pintype "passive"))
      (node (ref "R22a") (pin "2") (pinfunction "OUT_2") (pintype "passive"))
      (node (ref "U7a") (pin "4") (pintype "output"))
    )
    (net (code "43") (name "Net-(Pot2-Pad2)") (class "Default")
      (node (ref "Pot2") (pin "2") (pinfunction "2_2") (pintype "passive"))
      (node (ref "R13") (pin "2") (pinfunction "OUT_2") (pintype "passive"))
    )
    (net (code "44") (name "Net-(Pot2-Pad5)") (class "Default")
      (node (ref "Pot2") (pin "5") (pinfunction "5_5") (pintype "passive"))
      (node (ref "R13a") (pin "2") (pinfunction "OUT_2") (pintype "passive"))
    )
    (net (code "45") (name "Net-(Pot3-Pad2)") (class "Default")
      (node (ref "Pot3") (pin "2") (pinfunction "2_2") (pintype "passive"))
      (node (ref "R14") (pin "2") (pinfunction "OUT_2") (pintype "passive"))
    )
    (net (code "46") (name "Net-(Pot3-Pad3)") (class "Default")
      (node (ref "Pot3") (pin "3") (pinfunction "3_3") (pintype "passive"))
      (node (ref "R12") (pin "1") (pinfunction "OUT_1") (pintype "passive"))
    )
    (net (code "47") (name "Net-(Pot3-Pad5)") (class "Default")
      (node (ref "Pot3") (pin "5") (pinfunction "5_5") (pintype "passive"))
      (node (ref "R14a") (pin "2") (pinfunction "OUT_2") (pintype "passive"))
    )
    (net (code "48") (name "Net-(Pot3-Pad6)") (class "Default")
      (node (ref "Pot3") (pin "6") (pinfunction "6_6") (pintype "passive"))
      (node (ref "R12a") (pin "1") (pinfunction "OUT_1") (pintype "passive"))
    )
    (net (code "49") (name "Net-(Pot4-Pad1)") (class "Default")
      (node (ref "Pot4") (pin "1") (pinfunction "1_1") (pintype "passive"))
      (node (ref "R16") (pin "2") (pinfunction "OUT_2") (pintype "passive"))
      (node (ref "U6") (pin "1") (pintype "output"))
    )
    (net (code "50") (name "Net-(R15-OUT-Pad1)") (class "Default")
      (node (ref "R15") (pin "1") (pinfunction "OUT_1") (pintype "passive"))
      (node (ref "R17") (pin "2") (pinfunction "OUT_2") (pintype "passive"))
      (node (ref "U5") (pin "7") (pintype "output"))
    )
    (net (code "51") (name "Net-(R15a-OUT-Pad1)") (class "Default")
      (node (ref "R15a") (pin "1") (pinfunction "OUT_1") (pintype "passive"))
      (node (ref "R17a") (pin "2") (pinfunction "OUT_2") (pintype "passive"))
      (node (ref "U5") (pin "1") (pintype "output"))
    )
    (net (code "52") (name "Net-(U3A-+)") (class "Default")
      (node (ref "C6a") (pin "1") (pinfunction "1_1") (pintype "passive"))
      (node (ref "R10a") (pin "1") (pinfunction "OUT_1") (pintype "passive"))
      (node (ref "U3") (pin "3") (pinfunction "+_3") (pintype "input"))
    )
    (net (code "53") (name "Net-(U3A--)") (class "Default")
      (node (ref "C6a") (pin "2") (pinfunction "2_2") (pintype "passive"))
      (node (ref "R11a") (pin "2") (pinfunction "OUT_2") (pintype "passive"))
      (node (ref "R6a") (pin "1") (pinfunction "OUT_1") (pintype "passive"))
      (node (ref "U3") (pin "2") (pinfunction "-_2") (pintype "input"))
    )
    (net (code "54") (name "Net-(U3B-+)") (class "Default")
      (node (ref "C6") (pin "1") (pinfunction "1_1") (pintype "passive"))
      (node (ref "R10") (pin "1") (pinfunction "OUT_1") (pintype "passive"))
      (node (ref "U3") (pin "5") (pinfunction "+_5") (pintype "input"))
    )
    (net (code "55") (name "Net-(U3B--)") (class "Default")
      (node (ref "C6") (pin "2") (pinfunction "2_2") (pintype "passive"))
      (node (ref "R11") (pin "2") (pinfunction "OUT_2") (pintype "passive"))
      (node (ref "R6") (pin "1") (pinfunction "OUT_1") (pintype "passive"))
      (node (ref "U3") (pin "6") (pinfunction "-_6") (pintype "input"))
    )
    (net (code "56") (name "Net-(U4A--)") (class "Default")
      (node (ref "R13a") (pin "1") (pinfunction "OUT_1") (pintype "passive"))
      (node (ref "R8a") (pin "1") (pinfunction "OUT_1") (pintype "passive"))
      (node (ref "U4") (pin "2") (pinfunction "-_2") (pintype "input"))
    )
    (net (code "57") (name "Net-(U4B--)") (class "Default")
      (node (ref "R13") (pin "1") (pinfunction "OUT_1") (pintype "passive"))
      (node (ref "R8") (pin "1") (pinfunction "OUT_1") (pintype "passive"))
      (node (ref "U4") (pin "6") (pinfunction "-_6") (pintype "input"))
    )
    (net (code "58") (name "Net-(U5A--)") (class "Default")
      (node (ref "R14a") (pin "1") (pinfunction "OUT_1") (pintype "passive"))
      (node (ref "R15a") (pin "2") (pinfunction "OUT_2") (pintype "passive"))
      (node (ref "U5") (pin "2") (pinfunction "-_2") (pintype "input"))
    )
    (net (code "59") (name "Net-(U5B--)") (class "Default")
      (node (ref "R14") (pin "1") (pinfunction "OUT_1") (pintype "passive"))
      (node (ref "R15") (pin "2") (pinfunction "OUT_2") (pintype "passive"))
      (node (ref "U5") (pin "6") (pinfunction "-_6") (pintype "input"))
    )
    (net (code "60") (name "Net-(U6A--)") (class "Default")
      (node (ref "Pot4") (pin "2") (pinfunction "2_2") (pintype "passive"))
      (node (ref "Pot4") (pin "3") (pinfunction "3_3") (pintype "passive"))
      (node (ref "R2") (pin "2") (pinfunction "OUT_2") (pintype "passive"))
      (node (ref "R3") (pin "1") (pinfunction "OUT_1") (pintype "passive"))
      (node (ref "U6") (pin "2") (pinfunction "-_2") (pintype "input"))
    )
    (net (code "61") (name "Net-(U6B-+)") (class "Default")
      (node (ref "C19") (pin "1") (pinfunction "1_1") (pintype "passive"))
      (node (ref "R18") (pin "1") (pinfunction "OUT_1") (pintype "passive"))
      (node (ref "U6") (pin "5") (pinfunction "+_5") (pintype "input"))
    )
    (net (code "62") (name "Net-(U6B--)") (class "Default")
      (node (ref "C24") (pin "1") (pinfunction "1_1") (pintype "passive"))
      (node (ref "C25") (pin "2") (pinfunction "2_2") (pintype "passive"))
      (node (ref "U6") (pin "6") (pinfunction "-_6") (pintype "input"))
      (node (ref "U6") (pin "7") (pintype "output"))
    )
    (net (code "63") (name "Net-(U7-+)") (class "Default")
      (node (ref "C28") (pin "2") (pinfunction "2_2") (pintype "passive"))
      (node (ref "R20") (pin "1") (pinfunction "OUT_1") (pintype "passive"))
      (node (ref "U7") (pin "1") (pinfunction "+_1") (pintype "input"))
    )
    (net (code "64") (name "Net-(U7--)") (class "Default")
      (node (ref "R21") (pin "1") (pinfunction "OUT_1") (pintype "passive"))
      (node (ref "R22") (pin "2") (pinfunction "OUT_2") (pintype "passive"))
      (node (ref "U7") (pin "2") (pinfunction "-_2") (pintype "input"))
    )
    (net (code "65") (name "Net-(U7a-+)") (class "Default")
      (node (ref "C28a") (pin "2") (pinfunction "2_2") (pintype "passive"))
      (node (ref "R20a") (pin "1") (pinfunction "OUT_1") (pintype "passive"))
      (node (ref "U7a") (pin "1") (pinfunction "+_1") (pintype "input"))
    )
    (net (code "66") (name "Net-(U7a--)") (class "Default")
      (node (ref "R21a") (pin "1") (pinfunction "OUT_1") (pintype "passive"))
      (node (ref "R22a") (pin "1") (pinfunction "OUT_1") (pintype "passive"))
      (node (ref "U7a") (pin "2") (pinfunction "-_2") (pintype "input"))
    )
    (net (code "67") (name "Net-(U7b-+)") (class "Default")
      (node (ref "C28b") (pin "2") (pinfunction "2_2") (pintype "passive"))
      (node (ref "R20B") (pin "1") (pinfunction "OUT_1") (pintype "passive"))
      (node (ref "U7b") (pin "1") (pinfunction "+_1") (pintype "input"))
    )
    (net (code "68") (name "Net-(U7b--)") (class "Default")
      (node (ref "R21b") (pin "1") (pinfunction "OUT_1") (pintype "passive"))
      (node (ref "R22b") (pin "2") (pinfunction "OUT_2") (pintype "passive"))
      (node (ref "U7b") (pin "2") (pinfunction "-_2") (pintype "input"))
    )
  )
)
